# Button_and_more.net
KiCad netlist of a schematic drawn in Altium Designer
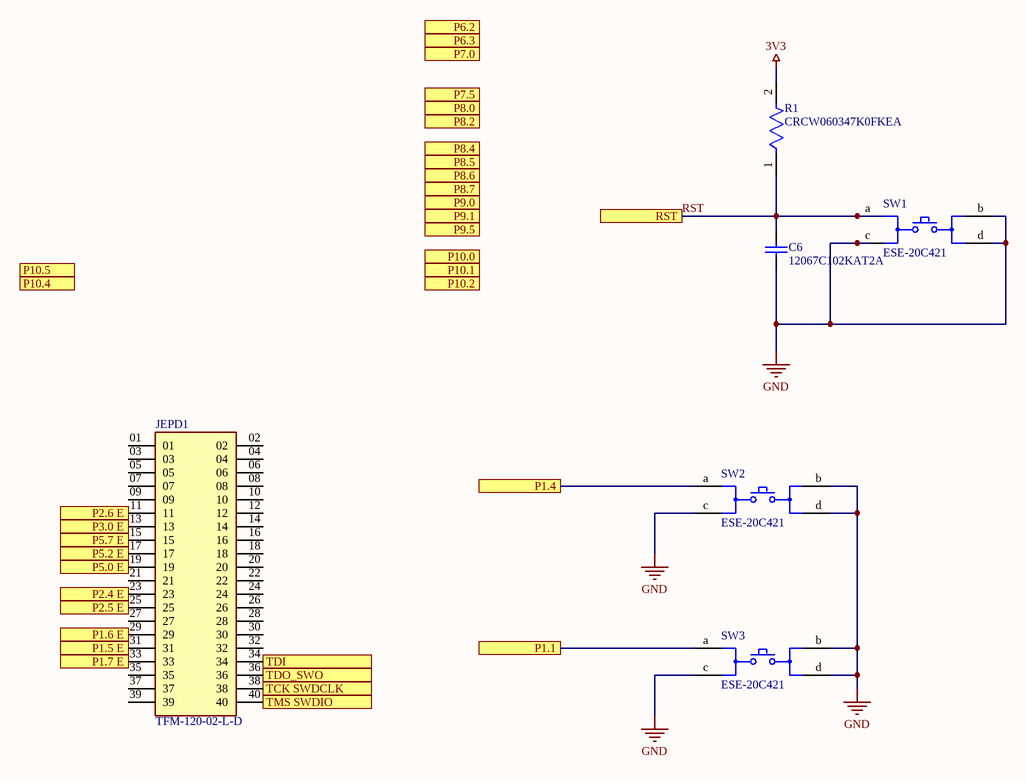
[diagram p0: Button and more.SchDoc]

(export (version "E")
  (design (tool "Eeschema 10.0.6"))
  (components
    (comp (ref "C6")
      (value "12067C102KAT2A")
      (footprint "CAPC3216X102X50LL20T25")
      (description "Chip Capacitor, 1 nF, +/- 10%, 500 V, -55 to 125 degC, 1206 (3216 Metric), RoHS, Tape and Reel")
      (fields (field (name "MANUFACTURER") "AVX"))
      (libsource (lib "Altium Content Vault") (part "CAP-NP-2"))
    )
    (comp (ref "JEPD1")
      (value "TFM-120-02-L-D")
      (footprint "SAMTEC_TFM-120-02-L-D")
      (fields (field (name "MF") "Samtec"))
      (libsource (lib "TFM-120-02-L-D") (part "TFM-120-02-L-D"))
    )
    (comp (ref "R1")
      (value "CRCW060347K0FKEA")
      (footprint "FP-CRCW0603-e3-MFG")
      (description "RES SMD 47K OHM 1% 1/10W 0603")
      (fields (field (name "TOLERANCE") "1%"))
      (libsource (lib "Altium Content Vault") (part "1029c3af85768c4190bb7ad29bc67b5"))
    )
    (comp (ref "SW1")
      (value "ESE-20C421")
      (footprint "FP-ESE-20C421-MFG")
      (description "SWITCH PUSH SPST-NO 0.1A 14V")
      (libsource (lib "Altium Content Vault") (part "eb2d96918082f90afa573f5ab447b27"))
    )
    (comp (ref "SW2")
      (value "ESE-20C421")
      (footprint "FP-ESE-20C421-MFG")
      (description "SWITCH PUSH SPST-NO 0.1A 14V")
      (libsource (lib "Altium Content Vault") (part "eb2d96918082f90afa573f5ab447b27"))
    )
    (comp (ref "SW3")
      (value "ESE-20C421")
      (footprint "FP-ESE-20C421-MFG")
      (description "SWITCH PUSH SPST-NO 0.1A 14V")
      (libsource (lib "Altium Content Vault") (part "eb2d96918082f90afa573f5ab447b27"))
    )
  )
  (nets
    (net (code "1") (name "/P1.1") (class "Default")
      (node (ref "SW3") (pin "a") (pinfunction "a_a") (pintype "passive"))
    )
    (net (code "2") (name "/P1.4") (class "Default")
      (node (ref "SW2") (pin "a") (pinfunction "a_a") (pintype "passive"))
    )
    (net (code "3") (name "/P1.5 E") (class "Default")
      (node (ref "JEPD1") (pin "31") (pinfunction "31_31") (pintype "passive"))
    )
    (net (code "4") (name "/P1.6 E") (class "Default")
      (node (ref "JEPD1") (pin "29") (pinfunction "29_29") (pintype "passive"))
    )
    (net (code "5") (name "/P1.7 E") (class "Default")
      (node (ref "JEPD1") (pin "33") (pinfunction "33_33") (pintype "passive"))
    )
    (net (code "6") (name "/P2.4 E") (class "Default")
      (node (ref "JEPD1") (pin "23") (pinfunction "23_23") (pintype "passive"))
    )
    (net (code "7") (name "/P2.5 E") (class "Default")
      (node (ref "JEPD1") (pin "25") (pinfunction "25_25") (pintype "passive"))
    )
    (net (code "8") (name "/P2.6 E") (class "Default")
      (node (ref "JEPD1") (pin "11") (pinfunction "11_11") (pintype "passive"))
    )
    (net (code "9") (name "/P3.0 E") (class "Default")
      (node (ref "JEPD1") (pin "13") (pinfunction "13_13") (pintype "passive"))
    )
    (net (code "10") (name "/P5.0 E") (class "Default")
      (node (ref "JEPD1") (pin "19") (pinfunction "19_19") (pintype "passive"))
    )
    (net (code "11") (name "/P5.2 E") (class "Default")
      (node (ref "JEPD1") (pin "17") (pinfunction "17_17") (pintype "passive"))
    )
    (net (code "12") (name "/P5.7 E") (class "Default")
      (node (ref "JEPD1") (pin "15") (pinfunction "15_15") (pintype "passive"))
    )
    (net (code "31") (name "/RST") (class "Default")
      (node (ref "C6") (pin "2") (pinfunction "2_2") (pintype "passive"))
      (node (ref "R1") (pin "1") (pinfunction "1_1") (pintype "passive"))
      (node (ref "SW1") (pin "a") (pinfunction "a_a") (pintype "passive"))
    )
    (net (code "32") (name "/TCK SWDCLK") (class "Default")
      (node (ref "JEPD1") (pin "38") (pinfunction "38_38") (pintype "passive"))
    )
    (net (code "33") (name "/TDI") (class "Default")
      (node (ref "JEPD1") (pin "34") (pinfunction "34_34") (pintype "passive"))
    )
    (net (code "34") (name "/TDO_SWO") (class "Default")
      (node (ref "JEPD1") (pin "36") (pinfunction "36_36") (pintype "passive"))
    )
    (net (code "35") (name "/TMS SWDIO") (class "Default")
      (node (ref "JEPD1") (pin "40") (pinfunction "40_40") (pintype "passive"))
    )
    (net (code "36") (name "3V3") (class "Default")
      (node (ref "R1") (pin "2") (pinfunction "2_2") (pintype "passive"))
    )
    (net (code "37") (name "GND") (class "Default")
      (node (ref "C6") (pin "1") (pinfunction "1_1") (pintype "passive"))
      (node (ref "SW1") (pin "b") (pinfunction "b_b") (pintype "passive"))
      (node (ref "SW1") (pin "c") (pinfunction "c_c") (pintype "passive"))
      (node (ref "SW1") (pin "d") (pinfunction "d_d") (pintype "passive"))
      (node (ref "SW2") (pin "b") (pinfunction "b_b") (pintype "passive"))
      (node (ref "SW2") (pin "c") (pinfunction "c_c") (pintype "passive"))
      (node (ref "SW2") (pin "d") (pinfunction "d_d") (pintype "passive"))
      (node (ref "SW3") (pin "b") (pinfunction "b_b") (pintype "passive"))
      (node (ref "SW3") (pin "c") (pinfunction "c_c") (pintype "passive"))
      (node (ref "SW3") (pin "d") (pinfunction "d_d") (pintype "passive"))
    )
    (net (code "38") (name "unconnected-(JEPD1-Pad01)") (class "Default")
      (node (ref "JEPD1") (pin "01") (pinfunction "01_01") (pintype "passive"))
    )
    (net (code "39") (name "unconnected-(JEPD1-Pad02)") (class "Default")
      (node (ref "JEPD1") (pin "02") (pinfunction "02_02") (pintype "passive"))
    )
    (net (code "40") (name "unconnected-(JEPD1-Pad03)") (class "Default")
      (node (ref "JEPD1") (pin "03") (pinfunction "03_03") (pintype "passive"))
    )
    (net (code "41") (name "unconnected-(JEPD1-Pad04)") (class "Default")
      (node (ref "JEPD1") (pin "04") (pinfunction "04_04") (pintype "passive"))
    )
    (net (code "42") (name "unconnected-(JEPD1-Pad05)") (class "Default")
      (node (ref "JEPD1") (pin "05") (pinfunction "05_05") (pintype "passive"))
    )
    (net (code "43") (name "unconnected-(JEPD1-Pad06)") (class "Default")
      (node (ref "JEPD1") (pin "06") (pinfunction "06_06") (pintype "passive"))
    )
    (net (code "44") (name "unconnected-(JEPD1-Pad07)") (class "Default")
      (node (ref "JEPD1") (pin "07") (pinfunction "07_07") (pintype "passive"))
    )
    (net (code "45") (name "unconnected-(JEPD1-Pad08)") (class "Default")
      (node (ref "JEPD1") (pin "08") (pinfunction "08_08") (pintype "passive"))
    )
    (net (code "46") (name "unconnected-(JEPD1-Pad09)") (class "Default")
      (node (ref "JEPD1") (pin "09") (pinfunction "09_09") (pintype "passive"))
    )
    (net (code "47") (name "unconnected-(JEPD1-Pad10)") (class "Default")
      (node (ref "JEPD1") (pin "10") (pinfunction "10_10") (pintype "passive"))
    )
    (net (code "48") (name "unconnected-(JEPD1-Pad12)") (class "Default")
      (node (ref "JEPD1") (pin "12") (pinfunction "12_12") (pintype "passive"))
    )
    (net (code "49") (name "unconnected-(JEPD1-Pad14)") (class "Default")
      (node (ref "JEPD1") (pin "14") (pinfunction "14_14") (pintype "passive"))
    )
    (net (code "50") (name "unconnected-(JEPD1-Pad16)") (class "Default")
      (node (ref "JEPD1") (pin "16") (pinfunction "16_16") (pintype "passive"))
    )
    (net (code "51") (name "unconnected-(JEPD1-Pad18)") (class "Default")
      (node (ref "JEPD1") (pin "18") (pinfunction "18_18") (pintype "passive"))
    )
    (net (code "52") (name "unconnected-(JEPD1-Pad20)") (class "Default")
      (node (ref "JEPD1") (pin "20") (pinfunction "20_20") (pintype "passive"))
    )
    (net (code "53") (name "unconnected-(JEPD1-Pad21)") (class "Default")
      (node (ref "JEPD1") (pin "21") (pinfunction "21_21") (pintype "passive"))
    )
    (net (code "54") (name "unconnected-(JEPD1-Pad22)") (class "Default")
      (node (ref "JEPD1") (pin "22") (pinfunction "22_22") (pintype "passive"))
    )
    (net (code "55") (name "unconnected-(JEPD1-Pad24)") (class "Default")
      (node (ref "JEPD1") (pin "24") (pinfunction "24_24") (pintype "passive"))
    )
    (net (code "56") (name "unconnected-(JEPD1-Pad26)") (class "Default")
      (node (ref "JEPD1") (pin "26") (pinfunction "26_26") (pintype "passive"))
    )
    (net (code "57") (name "unconnected-(JEPD1-Pad27)") (class "Default")
      (node (ref "JEPD1") (pin "27") (pinfunction "27_27") (pintype "passive"))
    )
    (net (code "58") (name "unconnected-(JEPD1-Pad28)") (class "Default")
      (node (ref "JEPD1") (pin "28") (pinfunction "28_28") (pintype "passive"))
    )
    (net (code "59") (name "unconnected-(JEPD1-Pad30)") (class "Default")
      (node (ref "JEPD1") (pin "30") (pinfunction "30_30") (pintype "passive"))
    )
    (net (code "60") (name "unconnected-(JEPD1-Pad32)") (class "Default")
      (node (ref "JEPD1") (pin "32") (pinfunction "32_32") (pintype "passive"))
    )
    (net (code "61") (name "unconnected-(JEPD1-Pad35)") (class "Default")
      (node (ref "JEPD1") (pin "35") (pinfunction "35_35") (pintype "passive"))
    )
    (net (code "62") (name "unconnected-(JEPD1-Pad37)") (class "Default")
      (node (ref "JEPD1") (pin "37") (pinfunction "37_37") (pintype "passive"))
    )
    (net (code "63") (name "unconnected-(JEPD1-Pad39)") (class "Default")
      (node (ref "JEPD1") (pin "39") (pinfunction "39_39") (pintype "passive"))
    )
  )
)
